# vga_ambilight_throughhole.net
KiCad netlist of a schematic drawn in EAGLE
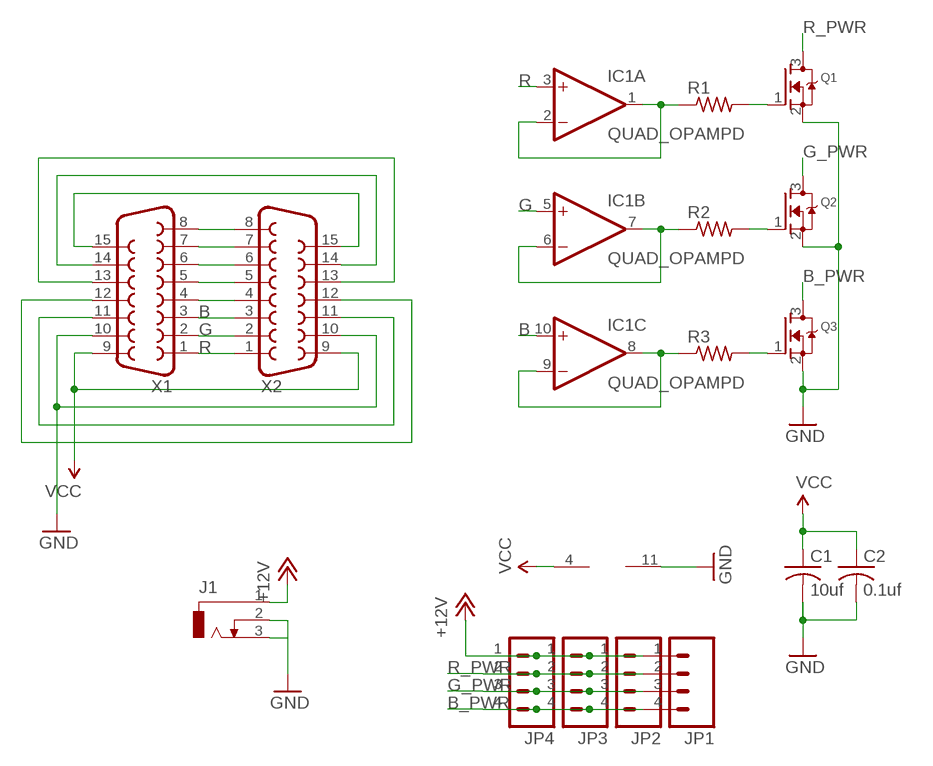
[diagram p0: schematic, sheet 1]

(export (version "E")
  (design (tool "Eeschema 10.0.6"))
  (components
    (comp (ref "C1")
      (value "10uf")
      (footprint "eagle-import:C1206")
      (libsource (lib "eagle-import") (part "C-USC1206"))
    )
    (comp (ref "C2")
      (value "0.1uf")
      (footprint "eagle-import:C1206")
      (libsource (lib "eagle-import") (part "C-USC1206"))
    )
    (comp (ref "IC1")
      (value "QUAD_OPAMPD")
      (footprint "eagle-import:SO14")
      (libsource (lib "eagle-import") (part "QUAD_OPAMPD"))
    )
    (comp (ref "J1")
      (value "DCJ0303")
      (footprint "eagle-import:DCJ0303")
      (libsource (lib "eagle-import") (part "DCJ0303"))
    )
    (comp (ref "JP1")
      (value "M04PTH")
      (footprint "eagle-import:1X04")
      (libsource (lib "eagle-import") (part "M04PTH"))
    )
    (comp (ref "JP2")
      (value "M04PTH")
      (footprint "eagle-import:1X04")
      (libsource (lib "eagle-import") (part "M04PTH"))
    )
    (comp (ref "JP3")
      (value "M04PTH")
      (footprint "eagle-import:1X04")
      (libsource (lib "eagle-import") (part "M04PTH"))
    )
    (comp (ref "JP4")
      (value "M04PTH")
      (footprint "eagle-import:1X04")
      (libsource (lib "eagle-import") (part "M04PTH"))
    )
    (comp (ref "Q1")
      (value "MOSFET-NREFLOW")
      (footprint "eagle-import:SOT23")
      (libsource (lib "eagle-import") (part "MOSFET-NREFLOW"))
    )
    (comp (ref "Q2")
      (value "MOSFET-NREFLOW")
      (footprint "eagle-import:SOT23")
      (libsource (lib "eagle-import") (part "MOSFET-NREFLOW"))
    )
    (comp (ref "Q3")
      (value "MOSFET-NREFLOW")
      (footprint "eagle-import:SOT23")
      (libsource (lib "eagle-import") (part "MOSFET-NREFLOW"))
    )
    (comp (ref "R1")
      (value "R-US_M0805")
      (footprint "eagle-import:M0805")
      (libsource (lib "eagle-import") (part "R-US_M0805"))
    )
    (comp (ref "R2")
      (value "R-US_M0805")
      (footprint "eagle-import:M0805")
      (libsource (lib "eagle-import") (part "R-US_M0805"))
    )
    (comp (ref "R3")
      (value "R-US_M0805")
      (footprint "eagle-import:M0805")
      (libsource (lib "eagle-import") (part "R-US_M0805"))
    )
    (comp (ref "X1")
      (value "F15HP")
      (footprint "eagle-import:F15HP")
      (libsource (lib "eagle-import") (part "F15HP"))
    )
    (comp (ref "X2")
      (value "F15HP")
      (footprint "eagle-import:F15HP")
      (libsource (lib "eagle-import") (part "F15HP"))
    )
  )
  (nets
    (net (code "1") (name "+12V") (class "Default")
      (node (ref "J1") (pin "1") (pinfunction "1_1") (pintype "passive"))
      (node (ref "JP1") (pin "1") (pinfunction "1_1") (pintype "passive"))
      (node (ref "JP2") (pin "1") (pinfunction "1_1") (pintype "passive"))
      (node (ref "JP3") (pin "1") (pinfunction "1_1") (pintype "passive"))
      (node (ref "JP4") (pin "1") (pinfunction "1_1") (pintype "passive"))
    )
    (net (code "2") (name "/B") (class "Default")
      (node (ref "IC1") (pin "10") (pinfunction "+IN_10") (pintype "input"))
      (node (ref "X1") (pin "3") (pinfunction "3_3") (pintype "passive"))
      (node (ref "X2") (pin "3") (pinfunction "3_3") (pintype "passive"))
    )
    (net (code "3") (name "/B_PWR") (class "Default")
      (node (ref "JP1") (pin "4") (pinfunction "4_4") (pintype "passive"))
      (node (ref "JP2") (pin "4") (pinfunction "4_4") (pintype "passive"))
      (node (ref "JP3") (pin "4") (pinfunction "4_4") (pintype "passive"))
      (node (ref "JP4") (pin "4") (pinfunction "4_4") (pintype "passive"))
      (node (ref "Q3") (pin "3") (pinfunction "D_3") (pintype "bidirectional"))
    )
    (net (code "4") (name "/G") (class "Default")
      (node (ref "IC1") (pin "5") (pinfunction "+IN_5") (pintype "input"))
      (node (ref "X1") (pin "2") (pinfunction "2_2") (pintype "passive"))
      (node (ref "X2") (pin "2") (pinfunction "2_2") (pintype "passive"))
    )
    (net (code "5") (name "/G_PWR") (class "Default")
      (node (ref "JP1") (pin "3") (pinfunction "3_3") (pintype "passive"))
      (node (ref "JP2") (pin "3") (pinfunction "3_3") (pintype "passive"))
      (node (ref "JP3") (pin "3") (pinfunction "3_3") (pintype "passive"))
      (node (ref "JP4") (pin "3") (pinfunction "3_3") (pintype "passive"))
      (node (ref "Q2") (pin "3") (pinfunction "D_3") (pintype "bidirectional"))
    )
    (net (code "6") (name "/R") (class "Default")
      (node (ref "IC1") (pin "3") (pinfunction "+IN_3") (pintype "input"))
      (node (ref "X1") (pin "1") (pinfunction "1_1") (pintype "passive"))
      (node (ref "X2") (pin "1") (pinfunction "1_1") (pintype "passive"))
    )
    (net (code "7") (name "/R_PWR") (class "Default")
      (node (ref "JP1") (pin "2") (pinfunction "2_2") (pintype "passive"))
      (node (ref "JP2") (pin "2") (pinfunction "2_2") (pintype "passive"))
      (node (ref "JP3") (pin "2") (pinfunction "2_2") (pintype "passive"))
      (node (ref "JP4") (pin "2") (pinfunction "2_2") (pintype "passive"))
      (node (ref "Q1") (pin "3") (pinfunction "D_3") (pintype "bidirectional"))
    )
    (net (code "8") (name "GND") (class "Default")
      (node (ref "C1") (pin "2") (pinfunction "2_2") (pintype "passive"))
      (node (ref "C2") (pin "2") (pinfunction "2_2") (pintype "passive"))
      (node (ref "IC1") (pin "11") (pinfunction "V-_11") (pintype "power_in"))
      (node (ref "J1") (pin "2") (pinfunction "2_2") (pintype "passive"))
      (node (ref "J1") (pin "3") (pinfunction "3_3") (pintype "passive"))
      (node (ref "Q1") (pin "2") (pinfunction "S_2") (pintype "bidirectional"))
      (node (ref "Q2") (pin "2") (pinfunction "S_2") (pintype "bidirectional"))
      (node (ref "Q3") (pin "2") (pinfunction "S_2") (pintype "bidirectional"))
      (node (ref "X1") (pin "10") (pinfunction "10_10") (pintype "passive"))
      (node (ref "X2") (pin "10") (pinfunction "10_10") (pintype "passive"))
    )
    (net (code "9") (name "Net-(IC1A--IN)") (class "Default")
      (node (ref "IC1") (pin "1") (pinfunction "OUT_1") (pintype "output"))
      (node (ref "IC1") (pin "2") (pinfunction "-IN_2") (pintype "input"))
      (node (ref "R1") (pin "1") (pinfunction "1_1") (pintype "passive"))
    )
    (net (code "10") (name "Net-(IC1B--IN)") (class "Default")
      (node (ref "IC1") (pin "6") (pinfunction "-IN_6") (pintype "input"))
      (node (ref "IC1") (pin "7") (pinfunction "OUT_7") (pintype "output"))
      (node (ref "R2") (pin "1") (pinfunction "1_1") (pintype "passive"))
    )
    (net (code "11") (name "Net-(IC1C--IN)") (class "Default")
      (node (ref "IC1") (pin "8") (pinfunction "OUT_8") (pintype "output"))
      (node (ref "IC1") (pin "9") (pinfunction "-IN_9") (pintype "input"))
      (node (ref "R3") (pin "1") (pinfunction "1_1") (pintype "passive"))
    )
    (net (code "12") (name "Net-(Q1-G)") (class "Default")
      (node (ref "Q1") (pin "1") (pinfunction "G_1") (pintype "bidirectional"))
      (node (ref "R1") (pin "2") (pinfunction "2_2") (pintype "passive"))
    )
    (net (code "13") (name "Net-(Q2-G)") (class "Default")
      (node (ref "Q2") (pin "1") (pinfunction "G_1") (pintype "bidirectional"))
      (node (ref "R2") (pin "2") (pinfunction "2_2") (pintype "passive"))
    )
    (net (code "14") (name "Net-(Q3-G)") (class "Default")
      (node (ref "Q3") (pin "1") (pinfunction "G_1") (pintype "bidirectional"))
      (node (ref "R3") (pin "2") (pinfunction "2_2") (pintype "passive"))
    )
    (net (code "15") (name "Net-(X1-Pad4)") (class "Default")
      (node (ref "X1") (pin "4") (pinfunction "4_4") (pintype "passive"))
      (node (ref "X2") (pin "4") (pinfunction "4_4") (pintype "passive"))
    )
    (net (code "16") (name "Net-(X1-Pad5)") (class "Default")
      (node (ref "X1") (pin "5") (pinfunction "5_5") (pintype "passive"))
      (node (ref "X2") (pin "5") (pinfunction "5_5") (pintype "passive"))
    )
    (net (code "17") (name "Net-(X1-Pad6)") (class "Default")
      (node (ref "X1") (pin "6") (pinfunction "6_6") (pintype "passive"))
      (node (ref "X2") (pin "6") (pinfunction "6_6") (pintype "passive"))
    )
    (net (code "18") (name "Net-(X1-Pad7)") (class "Default")
      (node (ref "X1") (pin "7") (pinfunction "7_7") (pintype "passive"))
      (node (ref "X2") (pin "7") (pinfunction "7_7") (pintype "passive"))
    )
    (net (code "19") (name "Net-(X1-Pad8)") (class "Default")
      (node (ref "X1") (pin "8") (pinfunction "8_8") (pintype "passive"))
      (node (ref "X2") (pin "8") (pinfunction "8_8") (pintype "passive"))
    )
    (net (code "20") (name "Net-(X1-Pad11)") (class "Default")
      (node (ref "X1") (pin "11") (pinfunction "11_11") (pintype "passive"))
      (node (ref "X2") (pin "11") (pinfunction "11_11") (pintype "passive"))
    )
    (net (code "21") (name "Net-(X1-Pad12)") (class "Default")
      (node (ref "X1") (pin "12") (pinfunction "12_12") (pintype "passive"))
      (node (ref "X2") (pin "12") (pinfunction "12_12") (pintype "passive"))
    )
    (net (code "22") (name "Net-(X1-Pad13)") (class "Default")
      (node (ref "X1") (pin "13") (pinfunction "13_13") (pintype "passive"))
      (node (ref "X2") (pin "13") (pinfunction "13_13") (pintype "passive"))
    )
    (net (code "23") (name "Net-(X1-Pad14)") (class "Default")
      (node (ref "X1") (pin "14") (pinfunction "14_14") (pintype "passive"))
      (node (ref "X2") (pin "14") (pinfunction "14_14") (pintype "passive"))
    )
    (net (code "24") (name "Net-(X1-Pad15)") (class "Default")
      (node (ref "X1") (pin "15") (pinfunction "15_15") (pintype "passive"))
      (node (ref "X2") (pin "15") (pinfunction "15_15") (pintype "passive"))
    )
    (net (code "25") (name "VCC") (class "Default")
      (node (ref "C1") (pin "1") (pinfunction "1_1") (pintype "passive"))
      (node (ref "C2") (pin "1") (pinfunction "1_1") (pintype "passive"))
      (node (ref "IC1") (pin "4") (pinfunction "V+_4") (pintype "power_in"))
      (node (ref "X1") (pin "9") (pinfunction "9_9") (pintype "passive"))
      (node (ref "X2") (pin "9") (pinfunction "9_9") (pintype "passive"))
    )
  )
)
